# 17-ECP5_FPGA_2.net
KiCad netlist of a schematic drawn in Altium Designer
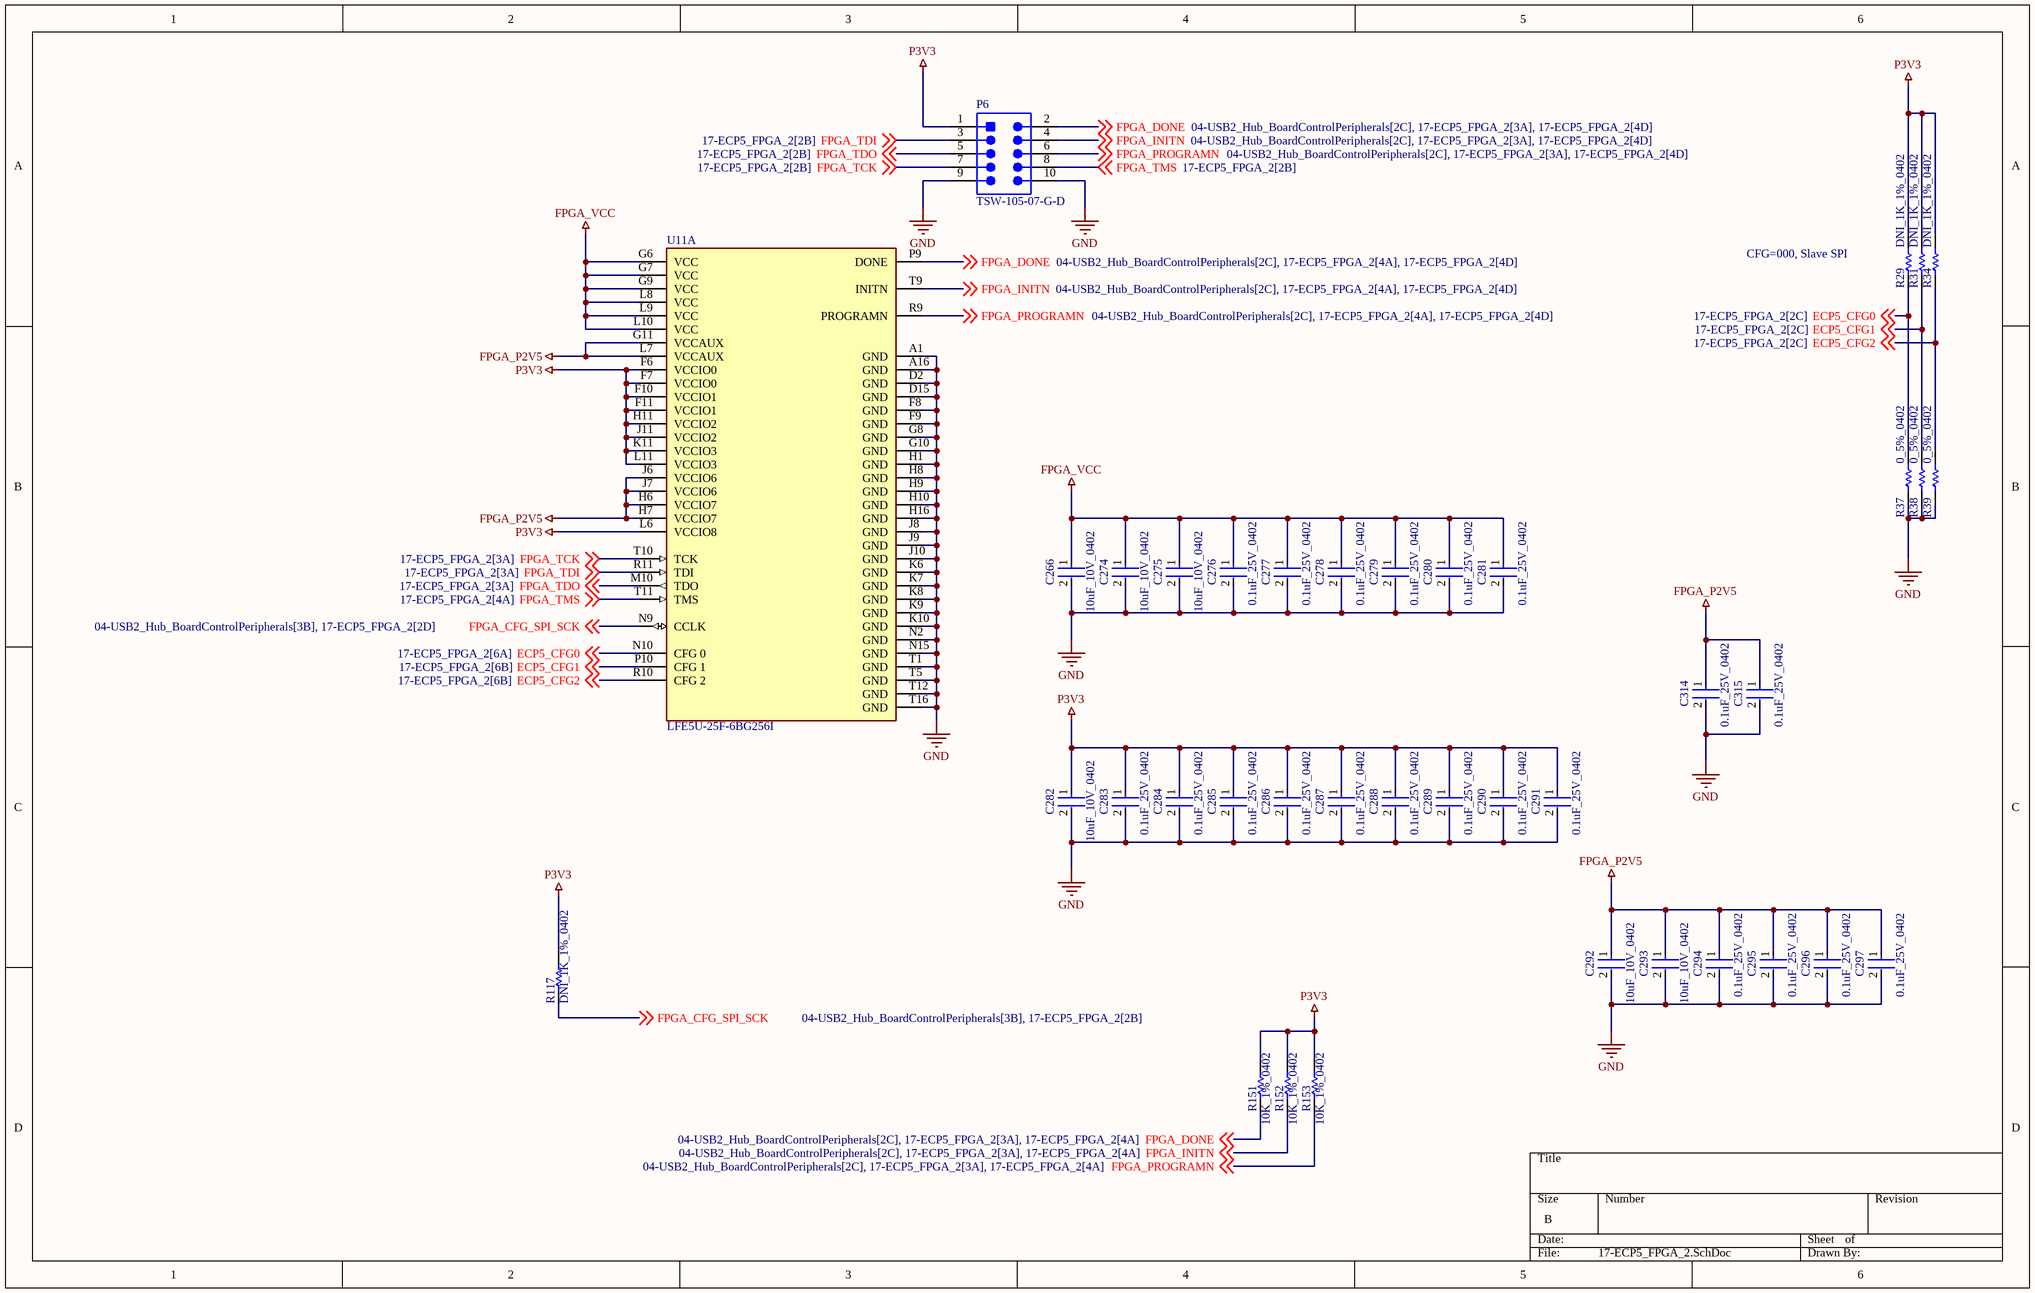
[diagram p0: 17-ECP5_FPGA_2.SchDoc]

(export (version "E")
  (design (tool "Eeschema 10.0.6"))
  (components
    (comp (ref "C266")
      (value "10uF_10V_0402")
      (footprint "FP-CL05A106MP5NUNC-MFG")
      (description "CAP CER 10UF 10V X5R 0402")
      (fields
        (field (name "OCTOPART") "https://octopart.com/cl05a106mp5nunc-samsung-22457395")
        (field (name "TOLERANCE") "20%")
      )
      (libsource (lib "Altium Content Vault") (part "b4654b650e69147ec39a6b967a45e02"))
    )
    (comp (ref "C274")
      (value "10uF_10V_0402")
      (footprint "FP-CL05A106MP5NUNC-MFG")
      (description "CAP CER 10UF 10V X5R 0402")
      (fields
        (field (name "OCTOPART") "https://octopart.com/cl05a106mp5nunc-samsung-22457395")
        (field (name "TOLERANCE") "20%")
      )
      (libsource (lib "Altium Content Vault") (part "b4654b650e69147ec39a6b967a45e02"))
    )
    (comp (ref "C275")
      (value "10uF_10V_0402")
      (footprint "FP-CL05A106MP5NUNC-MFG")
      (description "CAP CER 10UF 10V X5R 0402")
      (fields
        (field (name "OCTOPART") "https://octopart.com/cl05a106mp5nunc-samsung-22457395")
        (field (name "TOLERANCE") "20%")
      )
      (libsource (lib "Altium Content Vault") (part "b4654b650e69147ec39a6b967a45e02"))
    )
    (comp (ref "C276")
      (value "0.1uF_25V_0402")
      (footprint "FP-0402-L_1_0_1-W_0_5_0_1-IPC_C")
      (description "General Purpose Ceramic Capacitor, 0402, 100nF, 10%, X7R, 15%, 25V")
      (fields (field (name "VOLTAGE") "25V") (field (name "TOLERANCE") "10%"))
      (libsource (lib "Altium Content Vault") (part "b4654b650e69147ec39a6b967a45e02"))
    )
    (comp (ref "C277")
      (value "0.1uF_25V_0402")
      (footprint "FP-0402-L_1_0_1-W_0_5_0_1-IPC_C")
      (description "General Purpose Ceramic Capacitor, 0402, 100nF, 10%, X7R, 15%, 25V")
      (fields (field (name "VOLTAGE") "25V") (field (name "TOLERANCE") "10%"))
      (libsource (lib "Altium Content Vault") (part "b4654b650e69147ec39a6b967a45e02"))
    )
    (comp (ref "C278")
      (value "0.1uF_25V_0402")
      (footprint "FP-0402-L_1_0_1-W_0_5_0_1-IPC_C")
      (description "General Purpose Ceramic Capacitor, 0402, 100nF, 10%, X7R, 15%, 25V")
      (fields (field (name "VOLTAGE") "25V") (field (name "TOLERANCE") "10%"))
      (libsource (lib "Altium Content Vault") (part "b4654b650e69147ec39a6b967a45e02"))
    )
    (comp (ref "C279")
      (value "0.1uF_25V_0402")
      (footprint "FP-0402-L_1_0_1-W_0_5_0_1-IPC_C")
      (description "General Purpose Ceramic Capacitor, 0402, 100nF, 10%, X7R, 15%, 25V")
      (fields (field (name "VOLTAGE") "25V") (field (name "TOLERANCE") "10%"))
      (libsource (lib "Altium Content Vault") (part "b4654b650e69147ec39a6b967a45e02"))
    )
    (comp (ref "C280")
      (value "0.1uF_25V_0402")
      (footprint "FP-0402-L_1_0_1-W_0_5_0_1-IPC_C")
      (description "General Purpose Ceramic Capacitor, 0402, 100nF, 10%, X7R, 15%, 25V")
      (fields (field (name "VOLTAGE") "25V") (field (name "TOLERANCE") "10%"))
      (libsource (lib "Altium Content Vault") (part "b4654b650e69147ec39a6b967a45e02"))
    )
    (comp (ref "C281")
      (value "0.1uF_25V_0402")
      (footprint "FP-0402-L_1_0_1-W_0_5_0_1-IPC_C")
      (description "General Purpose Ceramic Capacitor, 0402, 100nF, 10%, X7R, 15%, 25V")
      (fields (field (name "VOLTAGE") "25V") (field (name "TOLERANCE") "10%"))
      (libsource (lib "Altium Content Vault") (part "b4654b650e69147ec39a6b967a45e02"))
    )
    (comp (ref "C282")
      (value "10uF_10V_0402")
      (footprint "FP-CL05A106MP5NUNC-MFG")
      (description "CAP CER 10UF 10V X5R 0402")
      (fields
        (field (name "OCTOPART") "https://octopart.com/cl05a106mp5nunc-samsung-22457395")
        (field (name "TOLERANCE") "20%")
      )
      (libsource (lib "Altium Content Vault") (part "b4654b650e69147ec39a6b967a45e02"))
    )
    (comp (ref "C283")
      (value "0.1uF_25V_0402")
      (footprint "FP-0402-L_1_0_1-W_0_5_0_1-IPC_C")
      (description "General Purpose Ceramic Capacitor, 0402, 100nF, 10%, X7R, 15%, 25V")
      (fields (field (name "VOLTAGE") "25V") (field (name "TOLERANCE") "10%"))
      (libsource (lib "Altium Content Vault") (part "b4654b650e69147ec39a6b967a45e02"))
    )
    (comp (ref "C284")
      (value "0.1uF_25V_0402")
      (footprint "FP-0402-L_1_0_1-W_0_5_0_1-IPC_C")
      (description "General Purpose Ceramic Capacitor, 0402, 100nF, 10%, X7R, 15%, 25V")
      (fields (field (name "VOLTAGE") "25V") (field (name "TOLERANCE") "10%"))
      (libsource (lib "Altium Content Vault") (part "b4654b650e69147ec39a6b967a45e02"))
    )
    (comp (ref "C285")
      (value "0.1uF_25V_0402")
      (footprint "FP-0402-L_1_0_1-W_0_5_0_1-IPC_C")
      (description "General Purpose Ceramic Capacitor, 0402, 100nF, 10%, X7R, 15%, 25V")
      (fields (field (name "VOLTAGE") "25V") (field (name "TOLERANCE") "10%"))
      (libsource (lib "Altium Content Vault") (part "b4654b650e69147ec39a6b967a45e02"))
    )
    (comp (ref "C286")
      (value "0.1uF_25V_0402")
      (footprint "FP-0402-L_1_0_1-W_0_5_0_1-IPC_C")
      (description "General Purpose Ceramic Capacitor, 0402, 100nF, 10%, X7R, 15%, 25V")
      (fields (field (name "VOLTAGE") "25V") (field (name "TOLERANCE") "10%"))
      (libsource (lib "Altium Content Vault") (part "b4654b650e69147ec39a6b967a45e02"))
    )
    (comp (ref "C287")
      (value "0.1uF_25V_0402")
      (footprint "FP-0402-L_1_0_1-W_0_5_0_1-IPC_C")
      (description "General Purpose Ceramic Capacitor, 0402, 100nF, 10%, X7R, 15%, 25V")
      (fields (field (name "VOLTAGE") "25V") (field (name "TOLERANCE") "10%"))
      (libsource (lib "Altium Content Vault") (part "b4654b650e69147ec39a6b967a45e02"))
    )
    (comp (ref "C288")
      (value "0.1uF_25V_0402")
      (footprint "FP-0402-L_1_0_1-W_0_5_0_1-IPC_C")
      (description "General Purpose Ceramic Capacitor, 0402, 100nF, 10%, X7R, 15%, 25V")
      (fields (field (name "VOLTAGE") "25V") (field (name "TOLERANCE") "10%"))
      (libsource (lib "Altium Content Vault") (part "b4654b650e69147ec39a6b967a45e02"))
    )
    (comp (ref "C289")
      (value "0.1uF_25V_0402")
      (footprint "FP-0402-L_1_0_1-W_0_5_0_1-IPC_C")
      (description "General Purpose Ceramic Capacitor, 0402, 100nF, 10%, X7R, 15%, 25V")
      (fields (field (name "VOLTAGE") "25V") (field (name "TOLERANCE") "10%"))
      (libsource (lib "Altium Content Vault") (part "b4654b650e69147ec39a6b967a45e02"))
    )
    (comp (ref "C290")
      (value "0.1uF_25V_0402")
      (footprint "FP-0402-L_1_0_1-W_0_5_0_1-IPC_C")
      (description "General Purpose Ceramic Capacitor, 0402, 100nF, 10%, X7R, 15%, 25V")
      (fields (field (name "VOLTAGE") "25V") (field (name "TOLERANCE") "10%"))
      (libsource (lib "Altium Content Vault") (part "b4654b650e69147ec39a6b967a45e02"))
    )
    (comp (ref "C291")
      (value "0.1uF_25V_0402")
      (footprint "FP-0402-L_1_0_1-W_0_5_0_1-IPC_C")
      (description "General Purpose Ceramic Capacitor, 0402, 100nF, 10%, X7R, 15%, 25V")
      (fields (field (name "VOLTAGE") "25V") (field (name "TOLERANCE") "10%"))
      (libsource (lib "Altium Content Vault") (part "b4654b650e69147ec39a6b967a45e02"))
    )
    (comp (ref "C292")
      (value "10uF_10V_0402")
      (footprint "FP-CL05A106MP5NUNC-MFG")
      (description "CAP CER 10UF 10V X5R 0402")
      (fields
        (field (name "OCTOPART") "https://octopart.com/cl05a106mp5nunc-samsung-22457395")
        (field (name "TOLERANCE") "20%")
      )
      (libsource (lib "Altium Content Vault") (part "b4654b650e69147ec39a6b967a45e02"))
    )
    (comp (ref "C293")
      (value "10uF_10V_0402")
      (footprint "FP-CL05A106MP5NUNC-MFG")
      (description "CAP CER 10UF 10V X5R 0402")
      (fields
        (field (name "OCTOPART") "https://octopart.com/cl05a106mp5nunc-samsung-22457395")
        (field (name "TOLERANCE") "20%")
      )
      (libsource (lib "Altium Content Vault") (part "b4654b650e69147ec39a6b967a45e02"))
    )
    (comp (ref "C294")
      (value "0.1uF_25V_0402")
      (footprint "FP-0402-L_1_0_1-W_0_5_0_1-IPC_C")
      (description "General Purpose Ceramic Capacitor, 0402, 100nF, 10%, X7R, 15%, 25V")
      (fields (field (name "VOLTAGE") "25V") (field (name "TOLERANCE") "10%"))
      (libsource (lib "Altium Content Vault") (part "b4654b650e69147ec39a6b967a45e02"))
    )
    (comp (ref "C295")
      (value "0.1uF_25V_0402")
      (footprint "FP-0402-L_1_0_1-W_0_5_0_1-IPC_C")
      (description "General Purpose Ceramic Capacitor, 0402, 100nF, 10%, X7R, 15%, 25V")
      (fields (field (name "VOLTAGE") "25V") (field (name "TOLERANCE") "10%"))
      (libsource (lib "Altium Content Vault") (part "b4654b650e69147ec39a6b967a45e02"))
    )
    (comp (ref "C296")
      (value "0.1uF_25V_0402")
      (footprint "FP-0402-L_1_0_1-W_0_5_0_1-IPC_C")
      (description "General Purpose Ceramic Capacitor, 0402, 100nF, 10%, X7R, 15%, 25V")
      (fields (field (name "VOLTAGE") "25V") (field (name "TOLERANCE") "10%"))
      (libsource (lib "Altium Content Vault") (part "b4654b650e69147ec39a6b967a45e02"))
    )
    (comp (ref "C297")
      (value "0.1uF_25V_0402")
      (footprint "FP-0402-L_1_0_1-W_0_5_0_1-IPC_C")
      (description "General Purpose Ceramic Capacitor, 0402, 100nF, 10%, X7R, 15%, 25V")
      (fields (field (name "VOLTAGE") "25V") (field (name "TOLERANCE") "10%"))
      (libsource (lib "Altium Content Vault") (part "b4654b650e69147ec39a6b967a45e02"))
    )
    (comp (ref "C314")
      (value "0.1uF_25V_0402")
      (footprint "FP-0402-L_1_0_1-W_0_5_0_1-IPC_C")
      (description "General Purpose Ceramic Capacitor, 0402, 100nF, 10%, X7R, 15%, 25V")
      (fields (field (name "VOLTAGE") "25V") (field (name "TOLERANCE") "10%"))
      (libsource (lib "Altium Content Vault") (part "b4654b650e69147ec39a6b967a45e02"))
    )
    (comp (ref "C315")
      (value "0.1uF_25V_0402")
      (footprint "FP-0402-L_1_0_1-W_0_5_0_1-IPC_C")
      (description "General Purpose Ceramic Capacitor, 0402, 100nF, 10%, X7R, 15%, 25V")
      (fields (field (name "VOLTAGE") "25V") (field (name "TOLERANCE") "10%"))
      (libsource (lib "Altium Content Vault") (part "b4654b650e69147ec39a6b967a45e02"))
    )
    (comp (ref "P6")
      (value "TSW-105-07-G-D")
      (footprint "SMTC-TSW-105-07-G-D_V")
      (fields (field (name "MANUFACTURER") "Samtec-Inc."))
      (libsource (lib "Altium Content Vault") (part "CN-2P-M-R10"))
    )
    (comp (ref "R29")
      (value "DNI_1K_1%_0402")
      (footprint "RESC1005X40X25LL05T10")
      (fields (field (name "PART NUMBER") "CRCW04021K00FKEDHP") (field (name "MANUFACTURER") "Vishay Dale"))
      (libsource (lib "Altium Content Vault") (part "RES"))
    )
    (comp (ref "R31")
      (value "DNI_1K_1%_0402")
      (footprint "RESC1005X40X25LL05T10")
      (fields (field (name "PART NUMBER") "CRCW04021K00FKEDHP") (field (name "MANUFACTURER") "Vishay Dale"))
      (libsource (lib "Altium Content Vault") (part "RES"))
    )
    (comp (ref "R34")
      (value "DNI_1K_1%_0402")
      (footprint "RESC1005X40X25LL05T10")
      (fields (field (name "PART NUMBER") "CRCW04021K00FKEDHP") (field (name "MANUFACTURER") "Vishay Dale"))
      (libsource (lib "Altium Content Vault") (part "RES"))
    )
    (comp (ref "R37")
      (value "0_5%_0402")
      (footprint "RESC1005X40X25LL10T10")
      (fields (field (name "MANUFACTURER") "KOA Speer") (field (name "PART NUMBER") "RK73Z1ETTP"))
      (libsource (lib "Altium Content Vault") (part "RES"))
    )
    (comp (ref "R38")
      (value "0_5%_0402")
      (footprint "RESC1005X40X25LL10T10")
      (fields (field (name "MANUFACTURER") "KOA Speer") (field (name "PART NUMBER") "RK73Z1ETTP"))
      (libsource (lib "Altium Content Vault") (part "RES"))
    )
    (comp (ref "R39")
      (value "0_5%_0402")
      (footprint "RESC1005X40X25LL10T10")
      (fields (field (name "MANUFACTURER") "KOA Speer") (field (name "PART NUMBER") "RK73Z1ETTP"))
      (libsource (lib "Altium Content Vault") (part "RES"))
    )
    (comp (ref "R117")
      (value "DNI_1K_1%_0402")
      (footprint "RESC1005X40X25LL05T10")
      (fields (field (name "PART NUMBER") "CRCW04021K00FKEDHP") (field (name "MANUFACTURER") "Vishay Dale"))
      (libsource (lib "Altium Content Vault") (part "RES"))
    )
    (comp (ref "R151")
      (value "10K_1%_0402")
      (footprint "RESC1005X40X25NL10T10")
      (fields (field (name "MANUFACTURER") "Bourns") (field (name "PART NUMBER") "CR0402-FX-1002GLF"))
      (libsource (lib "Altium Content Vault") (part "RES"))
    )
    (comp (ref "R152")
      (value "10K_1%_0402")
      (footprint "RESC1005X40X25NL10T10")
      (fields (field (name "MANUFACTURER") "Bourns") (field (name "PART NUMBER") "CR0402-FX-1002GLF"))
      (libsource (lib "Altium Content Vault") (part "RES"))
    )
    (comp (ref "R153")
      (value "10K_1%_0402")
      (footprint "RESC1005X40X25NL10T10")
      (fields (field (name "MANUFACTURER") "Bourns") (field (name "PART NUMBER") "CR0402-FX-1002GLF"))
      (libsource (lib "Altium Content Vault") (part "RES"))
    )
    (comp (ref "U11")
      (value "LFE5U-25F-6BG256I")
      (footprint "FP-LFE5U-25F-6BG256I-MFG")
      (description "IC FPGA 197 I/O 256CABGA")
      (libsource (lib "Altium Content Vault") (part "bfd34961a1b5a598594aee4faf9689d"))
    )
  )
  (nets
    (net (code "1") (name "ECP5_CFG0") (class "Default")
      (node (ref "R29") (pin "1") (pinfunction "1_1") (pintype "passive"))
      (node (ref "R37") (pin "2") (pinfunction "2_2") (pintype "passive"))
      (node (ref "U11") (pin "N10") (pinfunction "CFG_0_N10") (pintype "passive"))
    )
    (net (code "2") (name "ECP5_CFG1") (class "Default")
      (node (ref "R31") (pin "1") (pinfunction "1_1") (pintype "passive"))
      (node (ref "R38") (pin "2") (pinfunction "2_2") (pintype "passive"))
      (node (ref "U11") (pin "P10") (pinfunction "CFG_1_P10") (pintype "passive"))
    )
    (net (code "3") (name "ECP5_CFG2") (class "Default")
      (node (ref "R34") (pin "1") (pinfunction "1_1") (pintype "passive"))
      (node (ref "R39") (pin "2") (pinfunction "2_2") (pintype "passive"))
      (node (ref "U11") (pin "R10") (pinfunction "CFG_2_R10") (pintype "passive"))
    )
    (net (code "4") (name "FPGA_CFG_SPI_SCK") (class "Default")
      (node (ref "R117") (pin "1") (pinfunction "1_1") (pintype "passive"))
      (node (ref "U11") (pin "N9") (pinfunction "CCLK_N9") (pintype "bidirectional"))
    )
    (net (code "5") (name "FPGA_DONE") (class "Default")
      (node (ref "P6") (pin "2") (pinfunction "2_2") (pintype "passive"))
      (node (ref "R151") (pin "1") (pinfunction "1_1") (pintype "passive"))
      (node (ref "U11") (pin "P9") (pinfunction "DONE_P9") (pintype "passive"))
    )
    (net (code "6") (name "FPGA_INITN") (class "Default")
      (node (ref "P6") (pin "4") (pinfunction "4_4") (pintype "passive"))
      (node (ref "R152") (pin "1") (pinfunction "1_1") (pintype "passive"))
      (node (ref "U11") (pin "T9") (pinfunction "INITN_T9") (pintype "passive"))
    )
    (net (code "7") (name "FPGA_P2V5") (class "Default")
      (node (ref "C292") (pin "1") (pinfunction "1_1") (pintype "passive"))
      (node (ref "C293") (pin "1") (pinfunction "1_1") (pintype "passive"))
      (node (ref "C294") (pin "1") (pinfunction "1_1") (pintype "passive"))
      (node (ref "C295") (pin "1") (pinfunction "1_1") (pintype "passive"))
      (node (ref "C296") (pin "1") (pinfunction "1_1") (pintype "passive"))
      (node (ref "C297") (pin "1") (pinfunction "1_1") (pintype "passive"))
      (node (ref "C314") (pin "1") (pinfunction "1_1") (pintype "passive"))
      (node (ref "C315") (pin "1") (pinfunction "1_1") (pintype "passive"))
      (node (ref "U11") (pin "G11") (pinfunction "VCCAUX_G11") (pintype "power_in"))
      (node (ref "U11") (pin "H6") (pinfunction "VCCIO7_H6") (pintype "power_in"))
      (node (ref "U11") (pin "H7") (pinfunction "VCCIO7_H7") (pintype "power_in"))
      (node (ref "U11") (pin "J6") (pinfunction "VCCIO6_J6") (pintype "power_in"))
      (node (ref "U11") (pin "J7") (pinfunction "VCCIO6_J7") (pintype "power_in"))
      (node (ref "U11") (pin "L7") (pinfunction "VCCAUX_L7") (pintype "power_in"))
    )
    (net (code "8") (name "FPGA_PROGRAMN") (class "Default")
      (node (ref "P6") (pin "6") (pinfunction "6_6") (pintype "passive"))
      (node (ref "R153") (pin "1") (pinfunction "1_1") (pintype "passive"))
      (node (ref "U11") (pin "R9") (pinfunction "PROGRAMN_R9") (pintype "passive"))
    )
    (net (code "9") (name "FPGA_TCK") (class "Default")
      (node (ref "P6") (pin "7") (pinfunction "7_7") (pintype "passive"))
      (node (ref "U11") (pin "T10") (pinfunction "TCK_T10") (pintype "input"))
    )
    (net (code "10") (name "FPGA_TDI") (class "Default")
      (node (ref "P6") (pin "3") (pinfunction "3_3") (pintype "passive"))
      (node (ref "U11") (pin "R11") (pinfunction "TDI_R11") (pintype "input"))
    )
    (net (code "11") (name "FPGA_TDO") (class "Default")
      (node (ref "P6") (pin "5") (pinfunction "5_5") (pintype "passive"))
      (node (ref "U11") (pin "M10") (pinfunction "TDO_M10") (pintype "output"))
    )
    (net (code "12") (name "FPGA_TMS") (class "Default")
      (node (ref "P6") (pin "8") (pinfunction "8_8") (pintype "passive"))
      (node (ref "U11") (pin "T11") (pinfunction "TMS_T11") (pintype "input"))
    )
    (net (code "13") (name "FPGA_VCC") (class "Default")
      (node (ref "C266") (pin "1") (pinfunction "1_1") (pintype "passive"))
      (node (ref "C274") (pin "1") (pinfunction "1_1") (pintype "passive"))
      (node (ref "C275") (pin "1") (pinfunction "1_1") (pintype "passive"))
      (node (ref "C276") (pin "1") (pinfunction "1_1") (pintype "passive"))
      (node (ref "C277") (pin "1") (pinfunction "1_1") (pintype "passive"))
      (node (ref "C278") (pin "1") (pinfunction "1_1") (pintype "passive"))
      (node (ref "C279") (pin "1") (pinfunction "1_1") (pintype "passive"))
      (node (ref "C280") (pin "1") (pinfunction "1_1") (pintype "passive"))
      (node (ref "C281") (pin "1") (pinfunction "1_1") (pintype "passive"))
      (node (ref "U11") (pin "G6") (pinfunction "VCC_G6") (pintype "power_in"))
      (node (ref "U11") (pin "G7") (pinfunction "VCC_G7") (pintype "power_in"))
      (node (ref "U11") (pin "G9") (pinfunction "VCC_G9") (pintype "power_in"))
      (node (ref "U11") (pin "L10") (pinfunction "VCC_L10") (pintype "power_in"))
      (node (ref "U11") (pin "L8") (pinfunction "VCC_L8") (pintype "power_in"))
      (node (ref "U11") (pin "L9") (pinfunction "VCC_L9") (pintype "power_in"))
    )
    (net (code "14") (name "GND") (class "Default")
      (node (ref "C266") (pin "2") (pinfunction "2_2") (pintype "passive"))
      (node (ref "C274") (pin "2") (pinfunction "2_2") (pintype "passive"))
      (node (ref "C275") (pin "2") (pinfunction "2_2") (pintype "passive"))
      (node (ref "C276") (pin "2") (pinfunction "2_2") (pintype "passive"))
      (node (ref "C277") (pin "2") (pinfunction "2_2") (pintype "passive"))
      (node (ref "C278") (pin "2") (pinfunction "2_2") (pintype "passive"))
      (node (ref "C279") (pin "2") (pinfunction "2_2") (pintype "passive"))
      (node (ref "C280") (pin "2") (pinfunction "2_2") (pintype "passive"))
      (node (ref "C281") (pin "2") (pinfunction "2_2") (pintype "passive"))
      (node (ref "C282") (pin "2") (pinfunction "2_2") (pintype "passive"))
      (node (ref "C283") (pin "2") (pinfunction "2_2") (pintype "passive"))
      (node (ref "C284") (pin "2") (pinfunction "2_2") (pintype "passive"))
      (node (ref "C285") (pin "2") (pinfunction "2_2") (pintype "passive"))
      (node (ref "C286") (pin "2") (pinfunction "2_2") (pintype "passive"))
      (node (ref "C287") (pin "2") (pinfunction "2_2") (pintype "passive"))
      (node (ref "C288") (pin "2") (pinfunction "2_2") (pintype "passive"))
      (node (ref "C289") (pin "2") (pinfunction "2_2") (pintype "passive"))
      (node (ref "C290") (pin "2") (pinfunction "2_2") (pintype "passive"))
      (node (ref "C291") (pin "2") (pinfunction "2_2") (pintype "passive"))
      (node (ref "C292") (pin "2") (pinfunction "2_2") (pintype "passive"))
      (node (ref "C293") (pin "2") (pinfunction "2_2") (pintype "passive"))
      (node (ref "C294") (pin "2") (pinfunction "2_2") (pintype "passive"))
      (node (ref "C295") (pin "2") (pinfunction "2_2") (pintype "passive"))
      (node (ref "C296") (pin "2") (pinfunction "2_2") (pintype "passive"))
      (node (ref "C297") (pin "2") (pinfunction "2_2") (pintype "passive"))
      (node (ref "C314") (pin "2") (pinfunction "2_2") (pintype "passive"))
      (node (ref "C315") (pin "2") (pinfunction "2_2") (pintype "passive"))
      (node (ref "P6") (pin "10") (pinfunction "10_10") (pintype "passive"))
      (node (ref "P6") (pin "9") (pinfunction "9_9") (pintype "passive"))
      (node (ref "R37") (pin "1") (pinfunction "1_1") (pintype "passive"))
      (node (ref "R38") (pin "1") (pinfunction "1_1") (pintype "passive"))
      (node (ref "R39") (pin "1") (pinfunction "1_1") (pintype "passive"))
      (node (ref "U11") (pin "A1") (pinfunction "GND_A1") (pintype "power_in"))
      (node (ref "U11") (pin "A16") (pinfunction "GND_A16") (pintype "power_in"))
      (node (ref "U11") (pin "D15") (pinfunction "GND_D15") (pintype "power_in"))
      (node (ref "U11") (pin "D2") (pinfunction "GND_D2") (pintype "power_in"))
      (node (ref "U11") (pin "F8") (pinfunction "GND_F8") (pintype "power_in"))
      (node (ref "U11") (pin "F9") (pinfunction "GND_F9") (pintype "power_in"))
      (node (ref "U11") (pin "G10") (pinfunction "GND_G10") (pintype "power_in"))
      (node (ref "U11") (pin "G8") (pinfunction "GND_G8") (pintype "power_in"))
      (node (ref "U11") (pin "H1") (pinfunction "GND_H1") (pintype "power_in"))
      (node (ref "U11") (pin "H10") (pinfunction "GND_H10") (pintype "power_in"))
      (node (ref "U11") (pin "H16") (pinfunction "GND_H16") (pintype "power_in"))
      (node (ref "U11") (pin "H8") (pinfunction "GND_H8") (pintype "power_in"))
      (node (ref "U11") (pin "H9") (pinfunction "GND_H9") (pintype "power_in"))
      (node (ref "U11") (pin "J10") (pinfunction "GND_J10") (pintype "power_in"))
      (node (ref "U11") (pin "J8") (pinfunction "GND_J8") (pintype "power_in"))
      (node (ref "U11") (pin "J9") (pinfunction "GND_J9") (pintype "power_in"))
      (node (ref "U11") (pin "K10") (pinfunction "GND_K10") (pintype "power_in"))
      (node (ref "U11") (pin "K6") (pinfunction "GND_K6") (pintype "power_in"))
      (node (ref "U11") (pin "K7") (pinfunction "GND_K7") (pintype "power_in"))
      (node (ref "U11") (pin "K8") (pinfunction "GND_K8") (pintype "power_in"))
      (node (ref "U11") (pin "K9") (pinfunction "GND_K9") (pintype "power_in"))
      (node (ref "U11") (pin "N15") (pinfunction "GND_N15") (pintype "power_in"))
      (node (ref "U11") (pin "N2") (pinfunction "GND_N2") (pintype "power_in"))
      (node (ref "U11") (pin "T1") (pinfunction "GND_T1") (pintype "power_in"))
      (node (ref "U11") (pin "T12") (pinfunction "GND_T12") (pintype "power_in"))
      (node (ref "U11") (pin "T16") (pinfunction "GND_T16") (pintype "power_in"))
      (node (ref "U11") (pin "T5") (pinfunction "GND_T5") (pintype "power_in"))
    )
    (net (code "15") (name "P3V3") (class "Default")
      (node (ref "C282") (pin "1") (pinfunction "1_1") (pintype "passive"))
      (node (ref "C283") (pin "1") (pinfunction "1_1") (pintype "passive"))
      (node (ref "C284") (pin "1") (pinfunction "1_1") (pintype "passive"))
      (node (ref "C285") (pin "1") (pinfunction "1_1") (pintype "passive"))
      (node (ref "C286") (pin "1") (pinfunction "1_1") (pintype "passive"))
      (node (ref "C287") (pin "1") (pinfunction "1_1") (pintype "passive"))
      (node (ref "C288") (pin "1") (pinfunction "1_1") (pintype "passive"))
      (node (ref "C289") (pin "1") (pinfunction "1_1") (pintype "passive"))
      (node (ref "C290") (pin "1") (pinfunction "1_1") (pintype "passive"))
      (node (ref "C291") (pin "1") (pinfunction "1_1") (pintype "passive"))
      (node (ref "P6") (pin "1") (pinfunction "1_1") (pintype "passive"))
      (node (ref "R117") (pin "2") (pinfunction "2_2") (pintype "passive"))
      (node (ref "R151") (pin "2") (pinfunction "2_2") (pintype "passive"))
      (node (ref "R152") (pin "2") (pinfunction "2_2") (pintype "passive"))
      (node (ref "R153") (pin "2") (pinfunction "2_2") (pintype "passive"))
      (node (ref "R29") (pin "2") (pinfunction "2_2") (pintype "passive"))
      (node (ref "R31") (pin "2") (pinfunction "2_2") (pintype "passive"))
      (node (ref "R34") (pin "2") (pinfunction "2_2") (pintype "passive"))
      (node (ref "U11") (pin "F10") (pinfunction "VCCIO1_F10") (pintype "power_in"))
      (node (ref "U11") (pin "F11") (pinfunction "VCCIO1_F11") (pintype "power_in"))
      (node (ref "U11") (pin "F6") (pinfunction "VCCIO0_F6") (pintype "power_in"))
      (node (ref "U11") (pin "F7") (pinfunction "VCCIO0_F7") (pintype "power_in"))
      (node (ref "U11") (pin "H11") (pinfunction "VCCIO2_H11") (pintype "power_in"))
      (node (ref "U11") (pin "J11") (pinfunction "VCCIO2_J11") (pintype "power_in"))
      (node (ref "U11") (pin "K11") (pinfunction "VCCIO3_K11") (pintype "power_in"))
      (node (ref "U11") (pin "L11") (pinfunction "VCCIO3_L11") (pintype "power_in"))
      (node (ref "U11") (pin "L6") (pinfunction "VCCIO8_L6") (pintype "power_in"))
    )
  )
)
